# IMU_connection_board.net
KiCad netlist of a schematic drawn in EAGLE
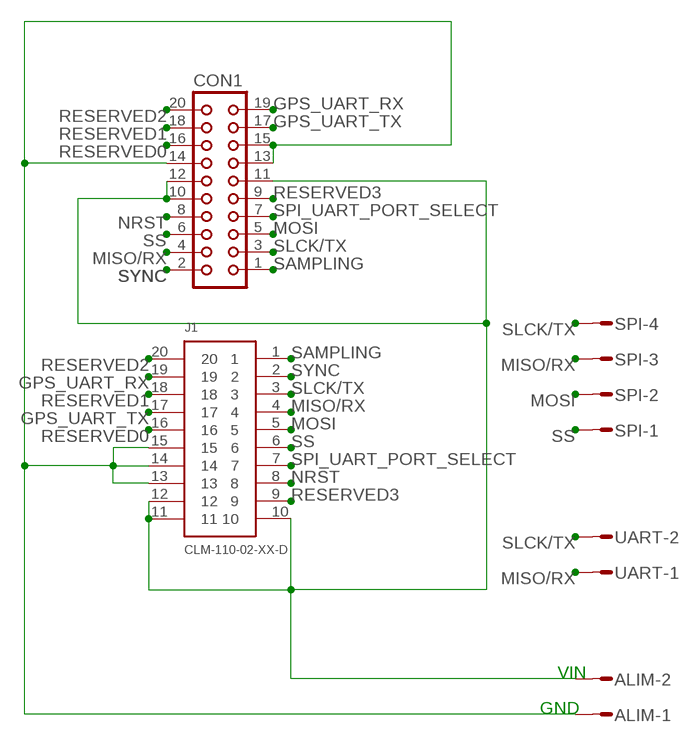
[diagram p0: schematic, sheet 1]

(export (version "E")
  (design (tool "Eeschema 10.0.6"))
  (components
    (comp (ref "ALIM")
      (value "L02P")
      (footprint "eagle-import:L02P")
      (libsource (lib "eagle-import") (part "L02P"))
    )
    (comp (ref "CON1")
      (value "CON20")
      (footprint "eagle-import:CON20")
      (libsource (lib "eagle-import") (part "CON20"))
    )
    (comp (ref "J1")
      (value "CLM-110-02-XX-D")
      (footprint "eagle-import:CLM-110-02-XX-D")
      (libsource (lib "eagle-import") (part "CLM-110-02-XX-D"))
    )
    (comp (ref "SPI")
      (value "L04P")
      (footprint "eagle-import:L04P")
      (libsource (lib "eagle-import") (part "L04P"))
    )
    (comp (ref "UART")
      (value "L02P")
      (footprint "eagle-import:L02P")
      (libsource (lib "eagle-import") (part "L02P"))
    )
  )
  (nets
    (net (code "1") (name "/GPS_UART_RX") (class "Default")
      (node (ref "CON1") (pin "19") (pinfunction "19_19") (pintype "passive"))
      (node (ref "J1") (pin "19") (pinfunction "19_19") (pintype "bidirectional"))
    )
    (net (code "2") (name "/GPS_UART_TX") (class "Default")
      (node (ref "CON1") (pin "17") (pinfunction "17_17") (pintype "passive"))
      (node (ref "J1") (pin "17") (pinfunction "17_17") (pintype "bidirectional"))
    )
    (net (code "3") (name "/MISO{slash}RX") (class "Default")
      (node (ref "CON1") (pin "4") (pinfunction "4_4") (pintype "passive"))
      (node (ref "J1") (pin "4") (pinfunction "4_4") (pintype "bidirectional"))
      (node (ref "SPI") (pin "3") (pinfunction "S_3") (pintype "passive"))
      (node (ref "UART") (pin "1") (pinfunction "S_1") (pintype "passive"))
    )
    (net (code "4") (name "/MOSI") (class "Default")
      (node (ref "CON1") (pin "5") (pinfunction "5_5") (pintype "passive"))
      (node (ref "J1") (pin "5") (pinfunction "5_5") (pintype "bidirectional"))
      (node (ref "SPI") (pin "2") (pinfunction "S_2") (pintype "passive"))
    )
    (net (code "5") (name "/NRST") (class "Default")
      (node (ref "CON1") (pin "8") (pinfunction "8_8") (pintype "passive"))
      (node (ref "J1") (pin "8") (pinfunction "8_8") (pintype "bidirectional"))
    )
    (net (code "6") (name "/RESERVED0") (class "Default")
      (node (ref "CON1") (pin "16") (pinfunction "16_16") (pintype "passive"))
      (node (ref "J1") (pin "16") (pinfunction "16_16") (pintype "bidirectional"))
    )
    (net (code "7") (name "/RESERVED1") (class "Default")
      (node (ref "CON1") (pin "18") (pinfunction "18_18") (pintype "passive"))
      (node (ref "J1") (pin "18") (pinfunction "18_18") (pintype "bidirectional"))
    )
    (net (code "8") (name "/RESERVED2") (class "Default")
      (node (ref "CON1") (pin "20") (pinfunction "20_20") (pintype "passive"))
      (node (ref "J1") (pin "20") (pinfunction "20_20") (pintype "bidirectional"))
    )
    (net (code "9") (name "/RESERVED3") (class "Default")
      (node (ref "CON1") (pin "9") (pinfunction "9_9") (pintype "passive"))
      (node (ref "J1") (pin "9") (pinfunction "9_9") (pintype "bidirectional"))
    )
    (net (code "10") (name "/SAMPLING") (class "Default")
      (node (ref "CON1") (pin "1") (pinfunction "1_1") (pintype "passive"))
      (node (ref "J1") (pin "1") (pinfunction "1_1") (pintype "bidirectional"))
    )
    (net (code "11") (name "/SLCK{slash}TX") (class "Default")
      (node (ref "CON1") (pin "3") (pinfunction "3_3") (pintype "passive"))
      (node (ref "J1") (pin "3") (pinfunction "3_3") (pintype "bidirectional"))
      (node (ref "SPI") (pin "4") (pinfunction "S_4") (pintype "passive"))
      (node (ref "UART") (pin "2") (pinfunction "S_2") (pintype "passive"))
    )
    (net (code "12") (name "/SPI_UART_PORT_SELECT") (class "Default")
      (node (ref "CON1") (pin "7") (pinfunction "7_7") (pintype "passive"))
      (node (ref "J1") (pin "7") (pinfunction "7_7") (pintype "bidirectional"))
    )
    (net (code "13") (name "/SS") (class "Default")
      (node (ref "CON1") (pin "6") (pinfunction "6_6") (pintype "passive"))
      (node (ref "J1") (pin "6") (pinfunction "6_6") (pintype "bidirectional"))
      (node (ref "SPI") (pin "1") (pinfunction "S_1") (pintype "passive"))
    )
    (net (code "14") (name "/SYNC") (class "Default")
      (node (ref "CON1") (pin "2") (pinfunction "2_2") (pintype "passive"))
      (node (ref "J1") (pin "2") (pinfunction "2_2") (pintype "bidirectional"))
    )
    (net (code "15") (name "Net-(ALIMA-S)") (class "Default")
      (node (ref "ALIM") (pin "1") (pinfunction "S_1") (pintype "passive"))
      (node (ref "CON1") (pin "13") (pinfunction "13_13") (pintype "passive"))
      (node (ref "CON1") (pin "14") (pinfunction "14_14") (pintype "passive"))
      (node (ref "CON1") (pin "15") (pinfunction "15_15") (pintype "passive"))
      (node (ref "J1") (pin "13") (pinfunction "13_13") (pintype "bidirectional"))
      (node (ref "J1") (pin "14") (pinfunction "14_14") (pintype "bidirectional"))
      (node (ref "J1") (pin "15") (pinfunction "15_15") (pintype "bidirectional"))
    )
    (net (code "16") (name "Net-(ALIMB-S)") (class "Default")
      (node (ref "ALIM") (pin "2") (pinfunction "S_2") (pintype "passive"))
      (node (ref "CON1") (pin "10") (pinfunction "10_10") (pintype "passive"))
      (node (ref "CON1") (pin "11") (pinfunction "11_11") (pintype "passive"))
      (node (ref "CON1") (pin "12") (pinfunction "12_12") (pintype "passive"))
      (node (ref "J1") (pin "10") (pinfunction "10_10") (pintype "bidirectional"))
      (node (ref "J1") (pin "11") (pinfunction "11_11") (pintype "bidirectional"))
      (node (ref "J1") (pin "12") (pinfunction "12_12") (pintype "bidirectional"))
    )
  )
)
